# AC_Contactor_Switch.net
KiCad netlist of a schematic drawn in EasyEDA Pro
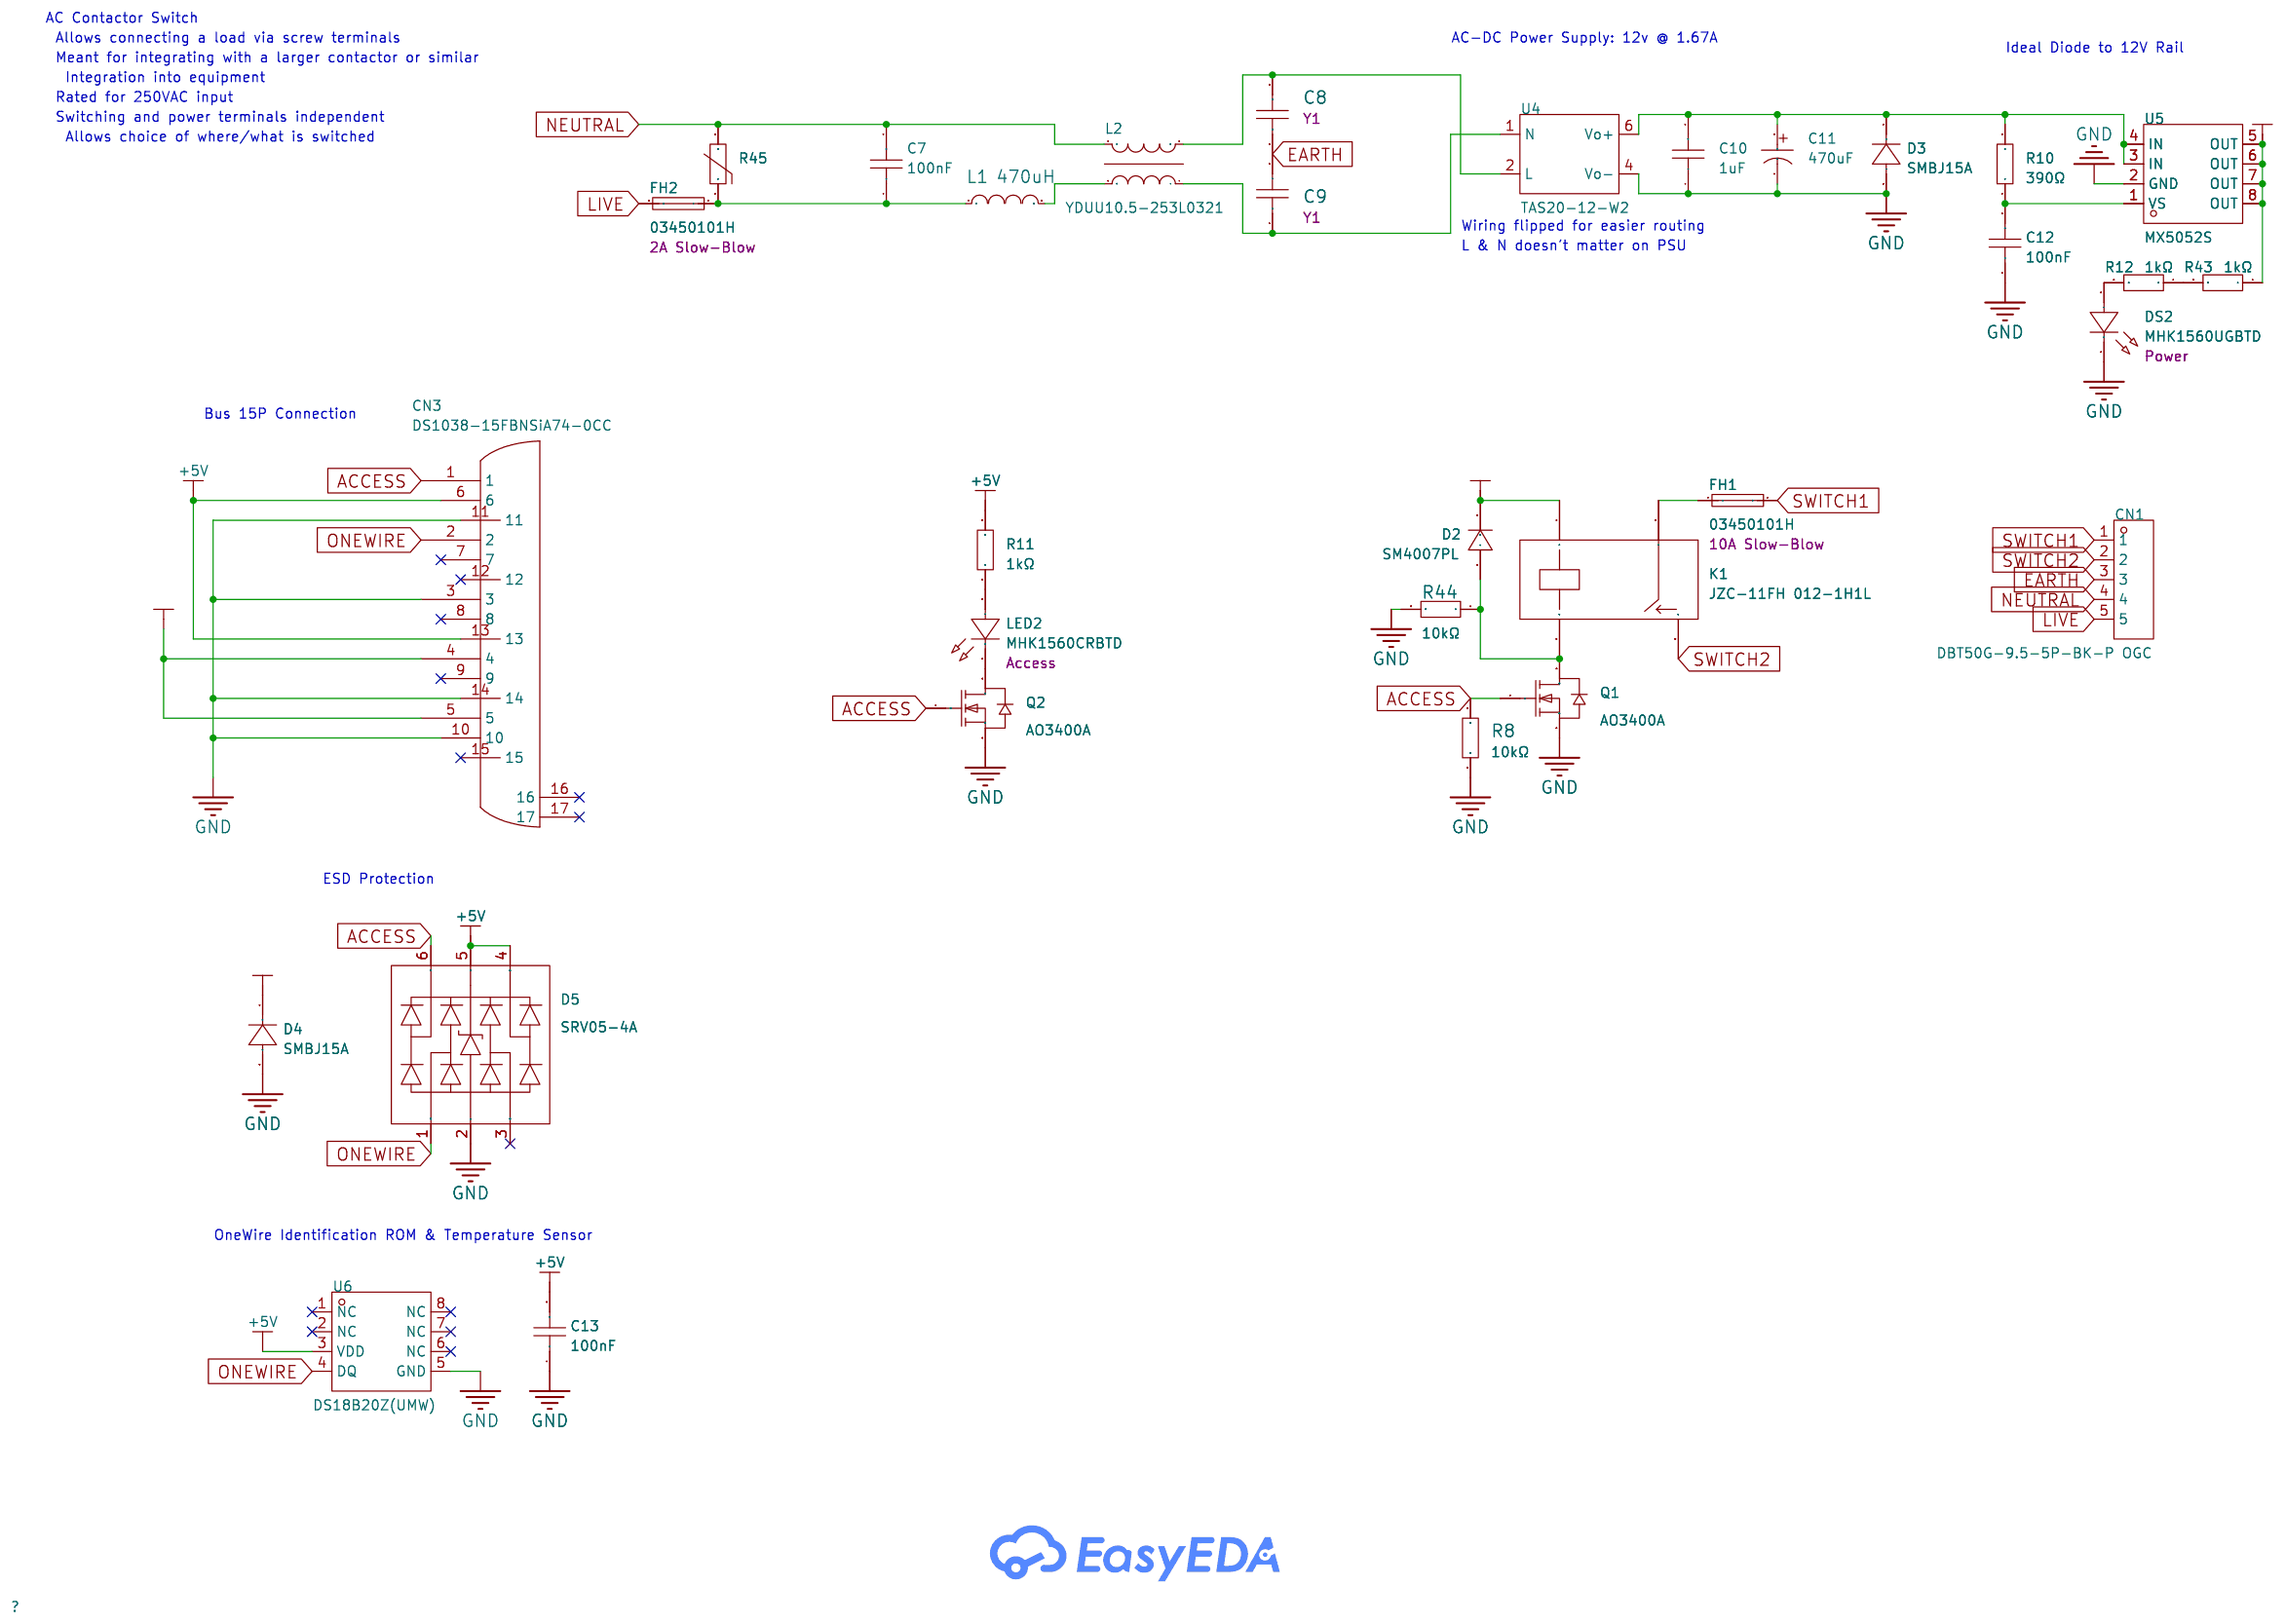
[diagram p0: schematic sheet]

(export (version "E")
  (design (tool "Eeschema 10.0.6"))
  (components
    (comp (ref "C7")
      (value "100nF")
      (footprint "easyedapro:CAP-TH_L10.0-W5.0-P7.50-D0.6")
      (fields (field (name "Manufacturer Part") "PX104K2C0702") (field (name "Manufacturer") "KYET(科雅)"))
      (libsource (lib "easyedapro") (part "PX104K2C0702"))
    )
    (comp (ref "C8")
      (value "1nF")
      (footprint "easyedapro:CAP-TH_L8.5-W5.0-P10.00-D0.6")
      (fields
        (field (name "Manufacturer Part") "VY1102M31Y5UC63V0")
        (field (name "Manufacturer") "VISHAY(威世)")
        (field (name "Ratings") "Y1")
      )
      (libsource (lib "easyedapro") (part "VY1102M31Y5UC63V0"))
    )
    (comp (ref "C9")
      (value "1nF")
      (footprint "easyedapro:CAP-TH_L8.5-W5.0-P10.00-D0.6")
      (fields
        (field (name "Manufacturer Part") "VY1102M31Y5UC63V0")
        (field (name "Manufacturer") "VISHAY(威世)")
        (field (name "Ratings") "Y1")
      )
      (libsource (lib "easyedapro") (part "VY1102M31Y5UC63V0"))
    )
    (comp (ref "C10")
      (value "1uF")
      (footprint "easyedapro:C0603")
      (description "Capacitance:1uF Tolerance:±10% Tolerance:±10% Voltage Rating:50V Temperature Coefficient:X5R")
      (fields
        (field (name "Manufacturer Part") "CL10A105KB8NNNC")
        (field (name "Manufacturer") "SAMSUNG(三星)")
      )
      (libsource (lib "easyedapro") (part "CL10A105KB8NNNC"))
    )
    (comp (ref "C11")
      (value "470uF")
      (footprint "easyedapro:CAP-TH_BD10.0-P5.00-D1.0-FD")
      (fields
        (field (name "Manufacturer Part") "KM477M025G13RR0VH2FP0")
        (field (name "Manufacturer") "Chengx(承兴)")
      )
      (libsource (lib "easyedapro") (part "470uF 25V 10*13"))
    )
    (comp (ref "C12")
      (value "100nF")
      (footprint "easyedapro:C0603")
      (description "Capacitance:100nF Tolerance:±10% Tolerance:±10% Voltage Rating:50V Temperature Coefficient:X7R")
      (fields
        (field (name "Manufacturer Part") "CC0603KRX7R9BB104")
        (field (name "Manufacturer") "YAGEO(国巨)")
      )
      (libsource (lib "easyedapro") (part "CC0603KRX7R9BB104"))
    )
    (comp (ref "C13")
      (value "100nF")
      (footprint "easyedapro:C0603")
      (description "Capacitance:100nF Tolerance:±10% Tolerance:±10% Voltage Rating:50V Temperature Coefficient:X7R")
      (fields
        (field (name "Manufacturer Part") "CC0603KRX7R9BB104")
        (field (name "Manufacturer") "YAGEO(国巨)")
      )
      (libsource (lib "easyedapro") (part "CC0603KRX7R9BB104"))
    )
    (comp (ref "CN1")
      (value "DBT50G-9.5-5P-BK-P OGC")
      (footprint "easyedapro:CONN-TH_5P-P9.50_DBT50G-9.5-5P")
      (fields (field (name "Manufacturer") "DORABO(地博电气)"))
      (libsource (lib "easyedapro") (part "DBT50G-9.5-5P"))
    )
    (comp (ref "CN3")
      (value "DS1038-15FBNSiA74-0CC")
      (footprint "easyedapro:DSUB-TH_DS1038-15FBNSIA74-0CC")
      (fields (field (name "Manufacturer") "CONNFLY"))
      (libsource (lib "easyedapro") (part "DS1038-15FBNSIA74-0CC"))
    )
    (comp (ref "D2")
      (value "SM4007PL")
      (footprint "easyedapro:SOD-123F_L2.8-W1.8-LS3.7-RD")
      (fields (field (name "Manufacturer") "MDD(辰达半导体)"))
      (libsource (lib "easyedapro") (part "SM4007PL"))
    )
    (comp (ref "D3")
      (value "SMBJ15A")
      (footprint "easyedapro:SMB_L4.3-W3.6-LS5.3-RD")
      (fields (field (name "Manufacturer") "R+O(宏嘉诚)"))
      (libsource (lib "easyedapro") (part "SMBJ15A_C19077569"))
    )
    (comp (ref "D4")
      (value "SMBJ15A")
      (footprint "easyedapro:SMB_L4.3-W3.6-LS5.3-RD")
      (fields (field (name "Manufacturer") "R+O(宏嘉诚)"))
      (libsource (lib "easyedapro") (part "SMBJ15A_C19077569"))
    )
    (comp (ref "D5")
      (value "SRV05-4A")
      (footprint "easyedapro:SOT-23-6_L2.9-W1.6-P0.95-LS2.9-BL")
      (fields (field (name "Manufacturer") "R+O(宏嘉诚)"))
      (libsource (lib "easyedapro") (part "SRV05-4A_C20615829"))
    )
    (comp (ref "DS2")
      (value "MHK1560UGBTD")
      (footprint "easyedapro:LED-TH_MHK1560UGBTD")
      (fields (field (name "Manufacturer") "MEIHUA(美华)") (field (name "Note") "Power"))
      (libsource (lib "easyedapro") (part "MHK1560UGBTD"))
    )
    (comp (ref "FH1")
      (value "03450101H")
      (footprint "easyedapro:03450101H")
      (fields (field (name "Manufacturer") "Littelfuse(美国力特)") (field (name "Note") "10A Slow-Blow"))
      (libsource (lib "easyedapro") (part "03450101H"))
    )
    (comp (ref "FH2")
      (value "03450101H")
      (footprint "easyedapro:03450101H")
      (fields (field (name "Manufacturer") "Littelfuse(美国力特)") (field (name "Note") "2A Slow-Blow"))
      (libsource (lib "easyedapro") (part "03450101H"))
    )
    (comp (ref "K1")
      (value "JZC-11FH 012-1H1L")
      (footprint "easyedapro:RELAY-TH_QLRELAY_JZC-11FH-XXX-1H1L")
      (fields (field (name "Manufacturer") "QLRELAY(群力)"))
      (libsource (lib "easyedapro") (part "JZC-11FH 012-1H1L"))
    )
    (comp (ref "L1")
      (value "470uH")
      (footprint "easyedapro:IND-TH_BD9.0-P5.00-D0.7")
      (fields (field (name "Manufacturer Part") "PK0810-471MB") (field (name "Manufacturer") "SXN(顺翔诺)"))
      (libsource (lib "easyedapro") (part "PK0810-471MB"))
    )
    (comp (ref "L2")
      (value "YDUU10.5-253L0321")
      (footprint "easyedapro:IND-TH_4P-L19.0-W17.0")
      (description "Number of Lines:2 Inductance @ Frequency:25mH@1KHz Voltage Withstand:1.5kV@AC")
      (fields (field (name "Manufacturer") "YJYCOIN(益嘉源)"))
      (libsource (lib "easyedapro") (part "YDUU10.5-253L0321"))
    )
    (comp (ref "LED2")
      (value "MHK1560CRBTD")
      (footprint "easyedapro:LED-TH_L12.2-W6.0-P2.54")
      (fields (field (name "Manufacturer") "MEIHUA(美华)") (field (name "Note") "Access"))
      (libsource (lib "easyedapro") (part "MHK1560CRBTD"))
    )
    (comp (ref "Q1")
      (value "AO3400A")
      (footprint "easyedapro:SOT-23-3_L2.9-W1.3-P1.90-LS2.4-BR")
      (fields (field (name "Manufacturer") "AOS"))
      (libsource (lib "easyedapro") (part "AO3400A"))
    )
    (comp (ref "Q2")
      (value "AO3400A")
      (footprint "easyedapro:SOT-23-3_L2.9-W1.3-P1.90-LS2.4-BR")
      (fields (field (name "Manufacturer") "AOS"))
      (libsource (lib "easyedapro") (part "AO3400A"))
    )
    (comp (ref "R8")
      (value "10kΩ")
      (footprint "easyedapro:R0603")
      (fields
        (field (name "Manufacturer Part") "0603WAF1002T5E")
        (field (name "Manufacturer") "UNI-ROYAL(厚声)")
      )
      (libsource (lib "easyedapro") (part "0603WAF1002T5E"))
    )
    (comp (ref "R10")
      (value "390Ω")
      (footprint "easyedapro:R0805")
      (fields
        (field (name "Manufacturer Part") "0805W8F3900T5E")
        (field (name "Manufacturer") "UNI-ROYAL(厚声)")
      )
      (libsource (lib "easyedapro") (part "0805W8F3900T5E"))
    )
    (comp (ref "R11")
      (value "1kΩ")
      (footprint "easyedapro:R0603")
      (fields
        (field (name "Manufacturer Part") "0603WAF1001T5E")
        (field (name "Manufacturer") "UNI-ROYAL(厚声)")
      )
      (libsource (lib "easyedapro") (part "0603WAF1001T5E"))
    )
    (comp (ref "R12")
      (value "1kΩ")
      (footprint "easyedapro:R0603")
      (fields
        (field (name "Manufacturer Part") "0603WAF1001T5E")
        (field (name "Manufacturer") "UNI-ROYAL(厚声)")
      )
      (libsource (lib "easyedapro") (part "0603WAF1001T5E"))
    )
    (comp (ref "R43")
      (value "1kΩ")
      (footprint "easyedapro:R0603")
      (fields
        (field (name "Manufacturer Part") "0603WAF1001T5E")
        (field (name "Manufacturer") "UNI-ROYAL(厚声)")
      )
      (libsource (lib "easyedapro") (part "0603WAF1001T5E"))
    )
    (comp (ref "R44")
      (value "10kΩ")
      (footprint "easyedapro:R0603")
      (fields
        (field (name "Manufacturer Part") "0603WAF1002T5E")
        (field (name "Manufacturer") "UNI-ROYAL(厚声)")
      )
      (libsource (lib "easyedapro") (part "0603WAF1002T5E"))
    )
    (comp (ref "R45")
      (value "210pF@1kHz")
      (footprint "easyedapro:RES-TH_L12.5-W5.1-P7.50-D1.2-S2.20")
      (fields (field (name "Manufacturer Part") "VDR-10D471K") (field (name "Manufacturer") "VDR(嵩隆)"))
      (libsource (lib "easyedapro") (part "VDR-10D471K"))
    )
    (comp (ref "U4")
      (value "TAS20-12-W2")
      (footprint "easyedapro:PWRM-TH_4P-L39.0-W25.0_TAS12-15-W2")
      (fields (field (name "Manufacturer") "TDPOWER(腾达电源)"))
      (libsource (lib "easyedapro") (part "TAS20-12-W2"))
    )
    (comp (ref "U5")
      (value "MX5052S")
      (footprint "easyedapro:SOP-8_L4.9-W3.9-P1.27-LS6.0-BL")
      (fields (field (name "Manufacturer") "Wuxi Maxinmicro(无锡明芯微)"))
      (libsource (lib "easyedapro") (part "MX5052S"))
    )
    (comp (ref "U6")
      (value "DS18B20Z(UMW)")
      (footprint "easyedapro:SOP-8_L4.9-W3.9-P1.27-LS6.0-BL")
      (fields (field (name "Manufacturer") "UMW(友台半导体)"))
      (libsource (lib "easyedapro") (part "DS18B20Z"))
    )
  )
  (nets
    (net (code "1") (name "+5V") (class "Default")
      (node (ref "C13") (pin "2") (pinfunction "2_2") (pintype "unspecified"))
      (node (ref "CN3") (pin "13") (pinfunction "13_13") (pintype "unspecified"))
      (node (ref "CN3") (pin "6") (pinfunction "6_6") (pintype "unspecified"))
      (node (ref "D5") (pin "4") (pinfunction "I/O_4") (pintype "unspecified"))
      (node (ref "D5") (pin "5") (pinfunction "VP_5") (pintype "unspecified"))
      (node (ref "R11") (pin "2") (pinfunction "2_2") (pintype "input"))
      (node (ref "U6") (pin "3") (pinfunction "VDD_3") (pintype "unspecified"))
    )
    (net (code "2") (name "+12V") (class "Default")
      (node (ref "CN3") (pin "4") (pinfunction "4_4") (pintype "unspecified"))
      (node (ref "CN3") (pin "5") (pinfunction "5_5") (pintype "unspecified"))
      (node (ref "D2") (pin "1") (pinfunction "C_1") (pintype "unspecified"))
      (node (ref "D4") (pin "1") (pinfunction "K_1") (pintype "unspecified"))
      (node (ref "K1") (pin "1") (pinfunction "1_1") (pintype "input"))
      (node (ref "R43") (pin "1") (pinfunction "1_1") (pintype "input"))
      (node (ref "U5") (pin "5") (pinfunction "OUT_5") (pintype "unspecified"))
      (node (ref "U5") (pin "6") (pinfunction "OUT_6") (pintype "unspecified"))
      (node (ref "U5") (pin "7") (pinfunction "OUT_7") (pintype "unspecified"))
      (node (ref "U5") (pin "8") (pinfunction "OUT_8") (pintype "unspecified"))
    )
    (net (code "3") (name "ACCESS") (class "Default")
      (node (ref "CN3") (pin "1") (pinfunction "1_1") (pintype "unspecified"))
      (node (ref "D5") (pin "6") (pinfunction "I/O_6") (pintype "unspecified"))
      (node (ref "Q1") (pin "1") (pinfunction "G_1") (pintype "unspecified"))
      (node (ref "Q2") (pin "1") (pinfunction "G_1") (pintype "unspecified"))
      (node (ref "R8") (pin "2") (pinfunction "2_2") (pintype "input"))
    )
    (net (code "4") (name "EARTH") (class "Default")
      (node (ref "C8") (pin "1") (pinfunction "1_1") (pintype "input"))
      (node (ref "C9") (pin "2") (pinfunction "2_2") (pintype "input"))
      (node (ref "CN1") (pin "3") (pinfunction "3_3") (pintype "unspecified"))
    )
    (net (code "5") (name "GND") (class "Default")
      (node (ref "C10") (pin "1") (pinfunction "1_1") (pintype "unspecified"))
      (node (ref "C11") (pin "2") (pinfunction "2_2") (pintype "input"))
      (node (ref "C12") (pin "1") (pinfunction "1_1") (pintype "unspecified"))
      (node (ref "C13") (pin "1") (pinfunction "1_1") (pintype "unspecified"))
      (node (ref "CN3") (pin "10") (pinfunction "10_10") (pintype "unspecified"))
      (node (ref "CN3") (pin "11") (pinfunction "11_11") (pintype "unspecified"))
      (node (ref "CN3") (pin "14") (pinfunction "14_14") (pintype "unspecified"))
      (node (ref "CN3") (pin "3") (pinfunction "3_3") (pintype "unspecified"))
      (node (ref "D3") (pin "2") (pinfunction "A_2") (pintype "unspecified"))
      (node (ref "D4") (pin "2") (pinfunction "A_2") (pintype "unspecified"))
      (node (ref "D5") (pin "2") (pinfunction "VN_2") (pintype "unspecified"))
      (node (ref "DS2") (pin "1") (pinfunction "K_1") (pintype "unspecified"))
      (node (ref "Q1") (pin "2") (pinfunction "S_2") (pintype "unspecified"))
      (node (ref "Q2") (pin "2") (pinfunction "S_2") (pintype "unspecified"))
      (node (ref "R44") (pin "2") (pinfunction "2_2") (pintype "input"))
      (node (ref "R8") (pin "1") (pinfunction "1_1") (pintype "input"))
      (node (ref "U4") (pin "4") (pinfunction "Vo-_4") (pintype "unspecified"))
      (node (ref "U5") (pin "2") (pinfunction "GND_2") (pintype "unspecified"))
      (node (ref "U6") (pin "5") (pinfunction "GND_5") (pintype "unspecified"))
    )
    (net (code "6") (name "LIVE") (class "Default")
      (node (ref "CN1") (pin "5") (pinfunction "5_5") (pintype "unspecified"))
      (node (ref "FH2") (pin "2") (pinfunction "2_2") (pintype "unspecified"))
    )
    (net (code "7") (name "NEUTRAL") (class "Default")
      (node (ref "C7") (pin "2") (pinfunction "2_2") (pintype "unspecified"))
      (node (ref "CN1") (pin "4") (pinfunction "4_4") (pintype "unspecified"))
      (node (ref "L2") (pin "1") (pinfunction "1_1") (pintype "unspecified"))
      (node (ref "R45") (pin "2") (pinfunction "2_2") (pintype "unspecified"))
    )
    (net (code "8") (name "Net-(C7-Pad1)") (class "Default")
      (node (ref "C7") (pin "1") (pinfunction "1_1") (pintype "unspecified"))
      (node (ref "FH2") (pin "1") (pinfunction "1_1") (pintype "unspecified"))
      (node (ref "L1") (pin "1") (pinfunction "1_1") (pintype "input"))
      (node (ref "R45") (pin "1") (pinfunction "1_1") (pintype "unspecified"))
    )
    (net (code "9") (name "Net-(D2-A)") (class "Default")
      (node (ref "D2") (pin "2") (pinfunction "A_2") (pintype "unspecified"))
      (node (ref "K1") (pin "2") (pinfunction "2_2") (pintype "input"))
      (node (ref "Q1") (pin "3") (pinfunction "D_3") (pintype "unspecified"))
      (node (ref "R44") (pin "1") (pinfunction "1_1") (pintype "input"))
    )
    (net (code "10") (name "Net-(D3-K)") (class "Default")
      (node (ref "C10") (pin "2") (pinfunction "2_2") (pintype "unspecified"))
      (node (ref "C11") (pin "1") (pinfunction "1_1") (pintype "input"))
      (node (ref "D3") (pin "1") (pinfunction "K_1") (pintype "unspecified"))
      (node (ref "R10") (pin "2") (pinfunction "2_2") (pintype "input"))
      (node (ref "U4") (pin "6") (pinfunction "Vo+_6") (pintype "unspecified"))
      (node (ref "U5") (pin "3") (pinfunction "IN_3") (pintype "unspecified"))
      (node (ref "U5") (pin "4") (pinfunction "IN_4") (pintype "unspecified"))
    )
    (net (code "11") (name "Net-(DS2-A)") (class "Default")
      (node (ref "DS2") (pin "2") (pinfunction "A_2") (pintype "unspecified"))
      (node (ref "R12") (pin "2") (pinfunction "2_2") (pintype "input"))
    )
    (net (code "12") (name "Net-(FH1-Pad1)") (class "Default")
      (node (ref "FH1") (pin "1") (pinfunction "1_1") (pintype "unspecified"))
      (node (ref "K1") (pin "4") (pinfunction "4_4") (pintype "input"))
    )
    (net (code "13") (name "Net-(L1-Pad2)") (class "Default")
      (node (ref "L1") (pin "2") (pinfunction "2_2") (pintype "input"))
      (node (ref "L2") (pin "2") (pinfunction "2_2") (pintype "unspecified"))
    )
    (net (code "14") (name "Net-(LED2-A)") (class "Default")
      (node (ref "LED2") (pin "2") (pinfunction "A_2") (pintype "unspecified"))
      (node (ref "R11") (pin "1") (pinfunction "1_1") (pintype "input"))
    )
    (net (code "15") (name "Net-(LED2-K)") (class "Default")
      (node (ref "LED2") (pin "1") (pinfunction "K_1") (pintype "unspecified"))
      (node (ref "Q2") (pin "3") (pinfunction "D_3") (pintype "unspecified"))
    )
    (net (code "16") (name "Net-(R12-Pad1)") (class "Default")
      (node (ref "R12") (pin "1") (pinfunction "1_1") (pintype "input"))
      (node (ref "R43") (pin "2") (pinfunction "2_2") (pintype "input"))
    )
    (net (code "17") (name "Net-(U4-L)") (class "Default")
      (node (ref "C8") (pin "2") (pinfunction "2_2") (pintype "input"))
      (node (ref "L2") (pin "3") (pinfunction "3_3") (pintype "unspecified"))
      (node (ref "U4") (pin "2") (pinfunction "L_2") (pintype "unspecified"))
    )
    (net (code "18") (name "Net-(U4-N)") (class "Default")
      (node (ref "C9") (pin "1") (pinfunction "1_1") (pintype "input"))
      (node (ref "L2") (pin "4") (pinfunction "4_4") (pintype "unspecified"))
      (node (ref "U4") (pin "1") (pinfunction "N_1") (pintype "unspecified"))
    )
    (net (code "19") (name "Net-(U5-VS)") (class "Default")
      (node (ref "C12") (pin "2") (pinfunction "2_2") (pintype "unspecified"))
      (node (ref "R10") (pin "1") (pinfunction "1_1") (pintype "input"))
      (node (ref "U5") (pin "1") (pinfunction "VS_1") (pintype "unspecified"))
    )
    (net (code "20") (name "ONEWIRE") (class "Default")
      (node (ref "CN3") (pin "2") (pinfunction "2_2") (pintype "unspecified"))
      (node (ref "D5") (pin "1") (pinfunction "I/O_1") (pintype "unspecified"))
      (node (ref "U6") (pin "4") (pinfunction "DQ_4") (pintype "unspecified"))
    )
    (net (code "21") (name "SWITCH1") (class "Default")
      (node (ref "CN1") (pin "1") (pinfunction "1_1") (pintype "unspecified"))
      (node (ref "FH1") (pin "2") (pinfunction "2_2") (pintype "unspecified"))
    )
    (net (code "22") (name "SWITCH2") (class "Default")
      (node (ref "CN1") (pin "2") (pinfunction "2_2") (pintype "unspecified"))
      (node (ref "K1") (pin "3") (pinfunction "3_3") (pintype "input"))
    )
    (net (code "23") (name "unconnected-(CN3-Pad7)") (class "Default")
      (node (ref "CN3") (pin "7") (pinfunction "7_7") (pintype "unspecified+no_connect"))
    )
    (net (code "24") (name "unconnected-(CN3-Pad8)") (class "Default")
      (node (ref "CN3") (pin "8") (pinfunction "8_8") (pintype "unspecified+no_connect"))
    )
    (net (code "25") (name "unconnected-(CN3-Pad9)") (class "Default")
      (node (ref "CN3") (pin "9") (pinfunction "9_9") (pintype "unspecified+no_connect"))
    )
    (net (code "26") (name "unconnected-(CN3-Pad12)") (class "Default")
      (node (ref "CN3") (pin "12") (pinfunction "12_12") (pintype "unspecified+no_connect"))
    )
    (net (code "27") (name "unconnected-(CN3-Pad15)") (class "Default")
      (node (ref "CN3") (pin "15") (pinfunction "15_15") (pintype "unspecified+no_connect"))
    )
    (net (code "28") (name "unconnected-(CN3-Pad16)") (class "Default")
      (node (ref "CN3") (pin "16") (pinfunction "16_16") (pintype "unspecified+no_connect"))
    )
    (net (code "29") (name "unconnected-(CN3-Pad17)") (class "Default")
      (node (ref "CN3") (pin "17") (pinfunction "17_17") (pintype "unspecified+no_connect"))
    )
    (net (code "30") (name "unconnected-(D5-I{slash}O-Pad3)") (class "Default")
      (node (ref "D5") (pin "3") (pinfunction "I/O_3") (pintype "unspecified+no_connect"))
    )
    (net (code "31") (name "unconnected-(U6-NC-Pad1)") (class "Default")
      (node (ref "U6") (pin "1") (pinfunction "NC_1") (pintype "unspecified+no_connect"))
    )
    (net (code "32") (name "unconnected-(U6-NC-Pad2)") (class "Default")
      (node (ref "U6") (pin "2") (pinfunction "NC_2") (pintype "unspecified+no_connect"))
    )
    (net (code "33") (name "unconnected-(U6-NC-Pad6)") (class "Default")
      (node (ref "U6") (pin "6") (pinfunction "NC_6") (pintype "unspecified+no_connect"))
    )
    (net (code "34") (name "unconnected-(U6-NC-Pad7)") (class "Default")
      (node (ref "U6") (pin "7") (pinfunction "NC_7") (pintype "unspecified+no_connect"))
    )
    (net (code "35") (name "unconnected-(U6-NC-Pad8)") (class "Default")
      (node (ref "U6") (pin "8") (pinfunction "NC_8") (pintype "unspecified+no_connect"))
    )
  )
)
